# BOWIE_FINGERS.net
KiCad netlist of a schematic drawn in Altium Designer
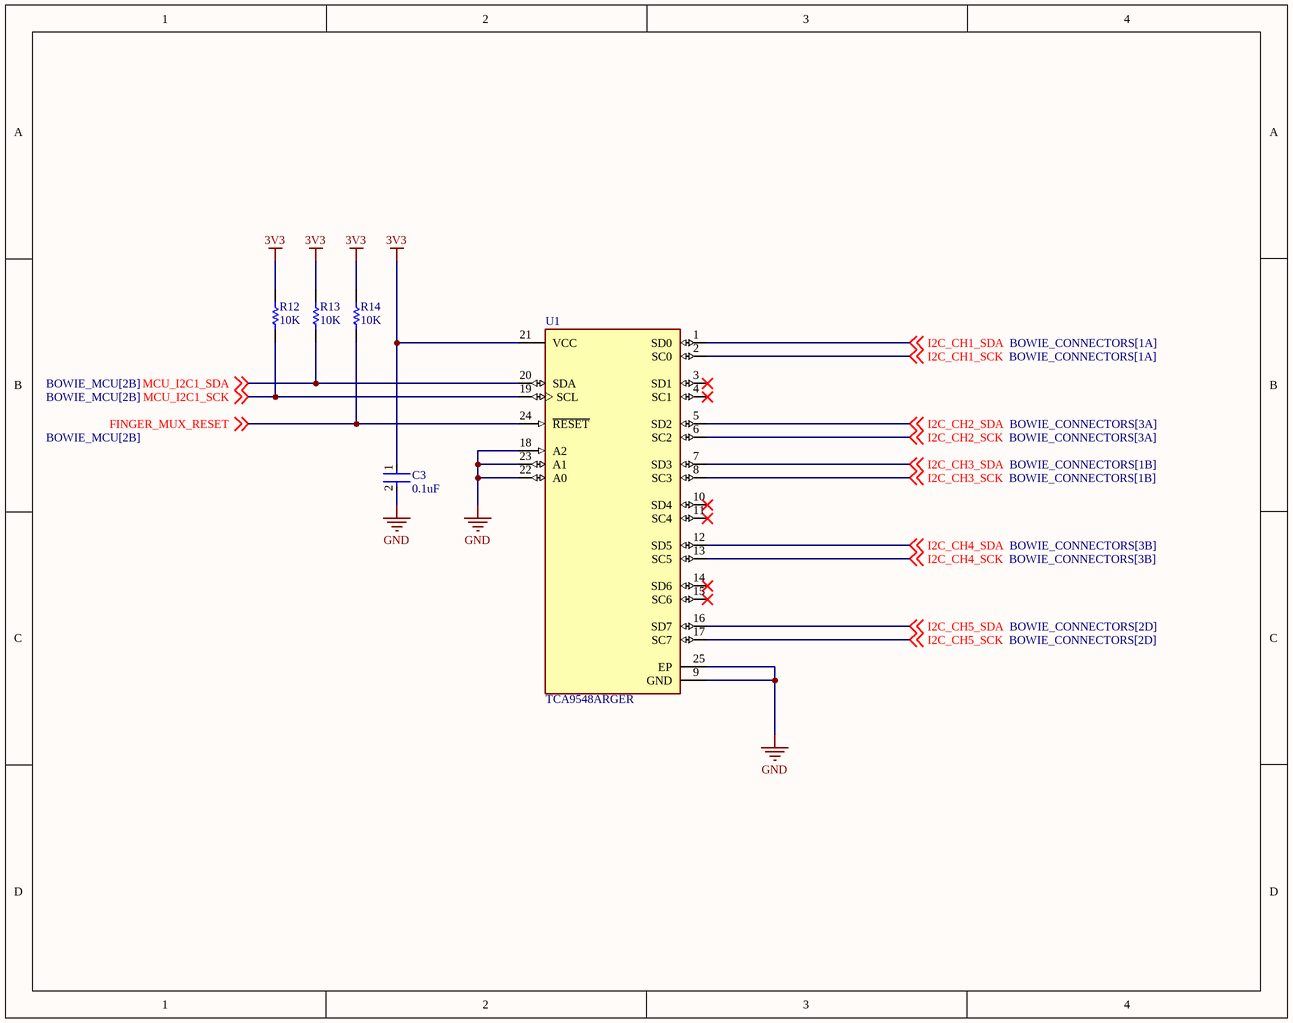
[diagram p0: BOWIE_FINGERS.SchDoc]

(export (version "E")
  (design (tool "Eeschema 10.0.6"))
  (components
    (comp (ref "C3")
      (value "0.1uF")
      (footprint "FP-GRM15-MFG")
      (description "CAP CER 0.1UF 16V X7R 0402")
      (fields (field (name "MANUFACTURER PART NUMBER") "GRM155R71C104KA88D") (field (name "TOLERANCE") "10%"))
      (libsource (lib "Altium Content Vault") (part "236180d848d6139a670b325ea6854c9"))
    )
    (comp (ref "R12")
      (value "10K")
      (footprint "RESC1005X40X25NL05T05")
      (description "Chip Resistor, 1 KOhm, +/- 1%, 100 mW, -55 to 155 degC, 0402 (1005 Metric), RoHS, Tape and Reel")
      (fields (field (name "PARTNUMBER") "ERJ-2RKF1001X") (field (name "MANUFACTURER") "Basic Passives"))
      (libsource (lib "Altium Content Vault") (part "RES-2"))
    )
    (comp (ref "R13")
      (value "10K")
      (footprint "RESC1005X40X25NL05T05")
      (description "Chip Resistor, 1 KOhm, +/- 1%, 100 mW, -55 to 155 degC, 0402 (1005 Metric), RoHS, Tape and Reel")
      (fields (field (name "PARTNUMBER") "ERJ-2RKF1001X") (field (name "MANUFACTURER") "Basic Passives"))
      (libsource (lib "Altium Content Vault") (part "RES-2"))
    )
    (comp (ref "R14")
      (value "10K")
      (footprint "RESC1005X40X25ML05T10")
      (fields (field (name "PART NUMBER") "CRCW040210K0FKEDHP") (field (name "MANUFACTURER") "Vishay Dale"))
      (libsource (lib "Altium Content Vault") (part "RES"))
    )
    (comp (ref "U1")
      (value "TCA9548ARGER")
      (footprint "FP-RGE0024C-MFG")
      (description "IC I2C SW 8CH W/RESET 24VQFN")
      (libsource (lib "Altium Content Vault") (part "87ad65078381ad6992a0152d7f2ce2c"))
    )
  )
  (nets
    (net (code "1") (name "3V3") (class "Default")
      (node (ref "C3") (pin "1") (pinfunction "1_1") (pintype "passive"))
      (node (ref "R12") (pin "2") (pinfunction "2_2") (pintype "passive"))
      (node (ref "R13") (pin "2") (pinfunction "2_2") (pintype "passive"))
      (node (ref "R14") (pin "2") (pinfunction "2_2") (pintype "passive"))
      (node (ref "U1") (pin "21") (pinfunction "VCC_21") (pintype "power_in"))
    )
    (net (code "2") (name "FINGER_MUX_RESET") (class "Default")
      (node (ref "R14") (pin "1") (pinfunction "1_1") (pintype "passive"))
      (node (ref "U1") (pin "24") (pinfunction "~{RESET}_24") (pintype "input"))
    )
    (net (code "3") (name "GND") (class "Default")
      (node (ref "C3") (pin "2") (pinfunction "2_2") (pintype "passive"))
      (node (ref "U1") (pin "18") (pinfunction "A2_18") (pintype "input"))
      (node (ref "U1") (pin "22") (pinfunction "A0_22") (pintype "bidirectional"))
      (node (ref "U1") (pin "23") (pinfunction "A1_23") (pintype "bidirectional"))
      (node (ref "U1") (pin "25") (pinfunction "EP_25") (pintype "power_in"))
      (node (ref "U1") (pin "9") (pinfunction "GND_9") (pintype "power_in"))
    )
    (net (code "4") (name "I2C_CH1_SCK") (class "Default")
      (node (ref "U1") (pin "2") (pinfunction "SC0_2") (pintype "bidirectional"))
    )
    (net (code "5") (name "I2C_CH1_SDA") (class "Default")
      (node (ref "U1") (pin "1") (pinfunction "SD0_1") (pintype "bidirectional"))
    )
    (net (code "6") (name "I2C_CH2_SCK") (class "Default")
      (node (ref "U1") (pin "6") (pinfunction "SC2_6") (pintype "bidirectional"))
    )
    (net (code "7") (name "I2C_CH2_SDA") (class "Default")
      (node (ref "U1") (pin "5") (pinfunction "SD2_5") (pintype "bidirectional"))
    )
    (net (code "8") (name "I2C_CH3_SCK") (class "Default")
      (node (ref "U1") (pin "8") (pinfunction "SC3_8") (pintype "bidirectional"))
    )
    (net (code "9") (name "I2C_CH3_SDA") (class "Default")
      (node (ref "U1") (pin "7") (pinfunction "SD3_7") (pintype "bidirectional"))
    )
    (net (code "10") (name "I2C_CH4_SCK") (class "Default")
      (node (ref "U1") (pin "13") (pinfunction "SC5_13") (pintype "bidirectional"))
    )
    (net (code "11") (name "I2C_CH4_SDA") (class "Default")
      (node (ref "U1") (pin "12") (pinfunction "SD5_12") (pintype "bidirectional"))
    )
    (net (code "12") (name "I2C_CH5_SCK") (class "Default")
      (node (ref "U1") (pin "17") (pinfunction "SC7_17") (pintype "bidirectional"))
    )
    (net (code "13") (name "I2C_CH5_SDA") (class "Default")
      (node (ref "U1") (pin "16") (pinfunction "SD7_16") (pintype "bidirectional"))
    )
    (net (code "14") (name "MCU_I2C1_SCK") (class "Default")
      (node (ref "R12") (pin "1") (pinfunction "1_1") (pintype "passive"))
      (node (ref "U1") (pin "19") (pinfunction "SCL_19") (pintype "bidirectional"))
    )
    (net (code "15") (name "MCU_I2C1_SDA") (class "Default")
      (node (ref "R13") (pin "1") (pinfunction "1_1") (pintype "passive"))
      (node (ref "U1") (pin "20") (pinfunction "SDA_20") (pintype "bidirectional"))
    )
    (net (code "16") (name "unconnected-(U1-SC1-Pad4)") (class "Default")
      (node (ref "U1") (pin "4") (pinfunction "SC1_4") (pintype "bidirectional+no_connect"))
    )
    (net (code "17") (name "unconnected-(U1-SC4-Pad11)") (class "Default")
      (node (ref "U1") (pin "11") (pinfunction "SC4_11") (pintype "bidirectional+no_connect"))
    )
    (net (code "18") (name "unconnected-(U1-SC6-Pad15)") (class "Default")
      (node (ref "U1") (pin "15") (pinfunction "SC6_15") (pintype "bidirectional+no_connect"))
    )
    (net (code "19") (name "unconnected-(U1-SD1-Pad3)") (class "Default")
      (node (ref "U1") (pin "3") (pinfunction "SD1_3") (pintype "bidirectional+no_connect"))
    )
    (net (code "20") (name "unconnected-(U1-SD4-Pad10)") (class "Default")
      (node (ref "U1") (pin "10") (pinfunction "SD4_10") (pintype "bidirectional+no_connect"))
    )
    (net (code "21") (name "unconnected-(U1-SD6-Pad14)") (class "Default")
      (node (ref "U1") (pin "14") (pinfunction "SD6_14") (pintype "bidirectional+no_connect"))
    )
  )
)
